# Layout_v1.net
KiCad netlist of a schematic drawn in Altium Designer
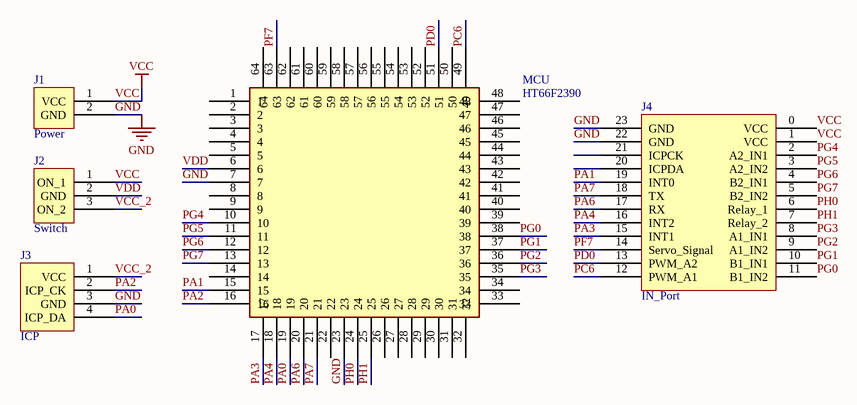
[diagram p0: Layout_v1.SchDoc]

(export (version "E")
  (design (tool "Eeschema 10.0.6"))
  (components
    (comp (ref "J1")
      (value "Power")
      (footprint "Layout_v1:Power_2P")
      (libsource (lib "Layout_v1") (part "Power"))
    )
    (comp (ref "J2")
      (value "Switch")
      (footprint "Layout_v1:Switch_3P")
      (libsource (lib "Layout_v1") (part "Switch"))
    )
    (comp (ref "J3") (value "ICP") (footprint "Layout_v1:ICP_4P") (libsource (lib "Layout_v1") (part "ICP")))
    (comp (ref "J4")
      (value "IN_Port")
      (footprint "Layout_v1:IC_Port_24P")
      (libsource (lib "Layout_v1") (part "IN_Port"))
    )
    (comp (ref "MCU")
      (value "HT66F2390")
      (footprint "Layout_v1:HT66F2390_64P")
      (libsource (lib "Layout_v1") (part "HT66F2390"))
    )
  )
  (nets
    (net (code "1") (name "/PA0") (class "Default")
      (node (ref "J3") (pin "4") (pinfunction "ICP_DA_4") (pintype "passive"))
      (node (ref "MCU") (pin "19") (pinfunction "19_19") (pintype "passive"))
    )
    (net (code "2") (name "/PA1") (class "Default")
      (node (ref "J4") (pin "19") (pinfunction "INT0_19") (pintype "passive"))
      (node (ref "MCU") (pin "15") (pinfunction "15_15") (pintype "passive"))
    )
    (net (code "3") (name "/PA2") (class "Default")
      (node (ref "J3") (pin "2") (pinfunction "ICP_CK_2") (pintype "passive"))
      (node (ref "MCU") (pin "16") (pinfunction "16_16") (pintype "passive"))
    )
    (net (code "4") (name "/PA3") (class "Default")
      (node (ref "J4") (pin "15") (pinfunction "INT1_15") (pintype "passive"))
      (node (ref "MCU") (pin "17") (pinfunction "17_17") (pintype "passive"))
    )
    (net (code "5") (name "/PA4") (class "Default")
      (node (ref "J4") (pin "16") (pinfunction "INT2_16") (pintype "passive"))
      (node (ref "MCU") (pin "18") (pinfunction "18_18") (pintype "passive"))
    )
    (net (code "6") (name "/PA6") (class "Default")
      (node (ref "J4") (pin "17") (pinfunction "RX_17") (pintype "passive"))
      (node (ref "MCU") (pin "20") (pinfunction "20_20") (pintype "passive"))
    )
    (net (code "7") (name "/PA7") (class "Default")
      (node (ref "J4") (pin "18") (pinfunction "TX_18") (pintype "passive"))
      (node (ref "MCU") (pin "21") (pinfunction "21_21") (pintype "passive"))
    )
    (net (code "8") (name "/PC6") (class "Default")
      (node (ref "J4") (pin "12") (pinfunction "PWM_A1_12") (pintype "passive"))
      (node (ref "MCU") (pin "49") (pinfunction "49_49") (pintype "passive"))
    )
    (net (code "9") (name "/PD0") (class "Default")
      (node (ref "J4") (pin "13") (pinfunction "PWM_A2_13") (pintype "passive"))
      (node (ref "MCU") (pin "51") (pinfunction "51_51") (pintype "passive"))
    )
    (net (code "10") (name "/PF7") (class "Default")
      (node (ref "J4") (pin "14") (pinfunction "Servo_Signal_14") (pintype "passive"))
      (node (ref "MCU") (pin "63") (pinfunction "63_63") (pintype "passive"))
    )
    (net (code "11") (name "/PG0") (class "Default")
      (node (ref "J4") (pin "11") (pinfunction "B1_IN2_11") (pintype "passive"))
      (node (ref "MCU") (pin "38") (pinfunction "38_38") (pintype "passive"))
    )
    (net (code "12") (name "/PG1") (class "Default")
      (node (ref "J4") (pin "10") (pinfunction "B1_IN1_10") (pintype "passive"))
      (node (ref "MCU") (pin "37") (pinfunction "37_37") (pintype "passive"))
    )
    (net (code "13") (name "/PG2") (class "Default")
      (node (ref "J4") (pin "9") (pinfunction "A1_IN2_9") (pintype "passive"))
      (node (ref "MCU") (pin "36") (pinfunction "36_36") (pintype "passive"))
    )
    (net (code "14") (name "/PG3") (class "Default")
      (node (ref "J4") (pin "8") (pinfunction "A1_IN1_8") (pintype "passive"))
      (node (ref "MCU") (pin "35") (pinfunction "35_35") (pintype "passive"))
    )
    (net (code "15") (name "/PG4") (class "Default")
      (node (ref "J4") (pin "2") (pinfunction "A2_IN1_2") (pintype "passive"))
      (node (ref "MCU") (pin "10") (pinfunction "10_10") (pintype "passive"))
    )
    (net (code "16") (name "/PG5") (class "Default")
      (node (ref "J4") (pin "3") (pinfunction "A2_IN2_3") (pintype "passive"))
      (node (ref "MCU") (pin "11") (pinfunction "11_11") (pintype "passive"))
    )
    (net (code "17") (name "/PG6") (class "Default")
      (node (ref "J4") (pin "4") (pinfunction "B2_IN1_4") (pintype "passive"))
      (node (ref "MCU") (pin "12") (pinfunction "12_12") (pintype "passive"))
    )
    (net (code "18") (name "/PG7") (class "Default")
      (node (ref "J4") (pin "5") (pinfunction "B2_IN2_5") (pintype "passive"))
      (node (ref "MCU") (pin "13") (pinfunction "13_13") (pintype "passive"))
    )
    (net (code "19") (name "/PH0") (class "Default")
      (node (ref "J4") (pin "6") (pinfunction "Relay_1_6") (pintype "passive"))
      (node (ref "MCU") (pin "24") (pinfunction "24_24") (pintype "passive"))
    )
    (net (code "20") (name "/PH1") (class "Default")
      (node (ref "J4") (pin "7") (pinfunction "Relay_2_7") (pintype "passive"))
      (node (ref "MCU") (pin "25") (pinfunction "25_25") (pintype "passive"))
    )
    (net (code "21") (name "/VCC_2") (class "Default")
      (node (ref "J2") (pin "3") (pinfunction "ON_2_3") (pintype "passive"))
      (node (ref "J3") (pin "1") (pinfunction "VCC_1") (pintype "passive"))
    )
    (net (code "22") (name "/VDD") (class "Default")
      (node (ref "J2") (pin "2") (pinfunction "GND_2") (pintype "passive"))
      (node (ref "MCU") (pin "6") (pinfunction "6_6") (pintype "passive"))
    )
    (net (code "23") (name "GND") (class "Default")
      (node (ref "J1") (pin "2") (pinfunction "GND_2") (pintype "passive"))
      (node (ref "J3") (pin "3") (pinfunction "GND_3") (pintype "passive"))
      (node (ref "J4") (pin "22") (pinfunction "GND_22") (pintype "passive"))
      (node (ref "J4") (pin "23") (pinfunction "GND_23") (pintype "passive"))
      (node (ref "MCU") (pin "23") (pinfunction "23_23") (pintype "passive"))
      (node (ref "MCU") (pin "7") (pinfunction "7_7") (pintype "passive"))
    )
    (net (code "24") (name "VCC") (class "Default")
      (node (ref "J1") (pin "1") (pinfunction "VCC_1") (pintype "passive"))
      (node (ref "J2") (pin "1") (pinfunction "ON_1_1") (pintype "passive"))
      (node (ref "J4") (pin "0") (pinfunction "VCC_0") (pintype "passive"))
      (node (ref "J4") (pin "1") (pinfunction "VCC_1") (pintype "passive"))
    )
    (net (code "25") (name "unconnected-(J4-ICPCK-Pad21)") (class "Default")
      (node (ref "J4") (pin "21") (pinfunction "ICPCK_21") (pintype "passive"))
    )
    (net (code "26") (name "unconnected-(J4-ICPDA-Pad20)") (class "Default")
      (node (ref "J4") (pin "20") (pinfunction "ICPDA_20") (pintype "passive"))
    )
    (net (code "27") (name "unconnected-(MCU-Pad1)") (class "Default")
      (node (ref "MCU") (pin "1") (pinfunction "1_1") (pintype "passive"))
    )
    (net (code "28") (name "unconnected-(MCU-Pad2)") (class "Default")
      (node (ref "MCU") (pin "2") (pinfunction "2_2") (pintype "passive"))
    )
    (net (code "29") (name "unconnected-(MCU-Pad3)") (class "Default")
      (node (ref "MCU") (pin "3") (pinfunction "3_3") (pintype "passive"))
    )
    (net (code "30") (name "unconnected-(MCU-Pad4)") (class "Default")
      (node (ref "MCU") (pin "4") (pinfunction "4_4") (pintype "passive"))
    )
    (net (code "31") (name "unconnected-(MCU-Pad5)") (class "Default")
      (node (ref "MCU") (pin "5") (pinfunction "5_5") (pintype "passive"))
    )
    (net (code "32") (name "unconnected-(MCU-Pad8)") (class "Default")
      (node (ref "MCU") (pin "8") (pinfunction "8_8") (pintype "passive"))
    )
    (net (code "33") (name "unconnected-(MCU-Pad9)") (class "Default")
      (node (ref "MCU") (pin "9") (pinfunction "9_9") (pintype "passive"))
    )
    (net (code "34") (name "unconnected-(MCU-Pad14)") (class "Default")
      (node (ref "MCU") (pin "14") (pinfunction "14_14") (pintype "passive"))
    )
    (net (code "35") (name "unconnected-(MCU-Pad22)") (class "Default")
      (node (ref "MCU") (pin "22") (pinfunction "22_22") (pintype "passive"))
    )
    (net (code "36") (name "unconnected-(MCU-Pad26)") (class "Default")
      (node (ref "MCU") (pin "26") (pinfunction "26_26") (pintype "passive"))
    )
    (net (code "37") (name "unconnected-(MCU-Pad27)") (class "Default")
      (node (ref "MCU") (pin "27") (pinfunction "27_27") (pintype "passive"))
    )
    (net (code "38") (name "unconnected-(MCU-Pad28)") (class "Default")
      (node (ref "MCU") (pin "28") (pinfunction "28_28") (pintype "passive"))
    )
    (net (code "39") (name "unconnected-(MCU-Pad29)") (class "Default")
      (node (ref "MCU") (pin "29") (pinfunction "29_29") (pintype "passive"))
    )
    (net (code "40") (name "unconnected-(MCU-Pad30)") (class "Default")
      (node (ref "MCU") (pin "30") (pinfunction "30_30") (pintype "passive"))
    )
    (net (code "41") (name "unconnected-(MCU-Pad31)") (class "Default")
      (node (ref "MCU") (pin "31") (pinfunction "31_31") (pintype "passive"))
    )
    (net (code "42") (name "unconnected-(MCU-Pad32)") (class "Default")
      (node (ref "MCU") (pin "32") (pinfunction "32_32") (pintype "passive"))
    )
    (net (code "43") (name "unconnected-(MCU-Pad33)") (class "Default")
      (node (ref "MCU") (pin "33") (pinfunction "33_33") (pintype "passive"))
    )
    (net (code "44") (name "unconnected-(MCU-Pad34)") (class "Default")
      (node (ref "MCU") (pin "34") (pinfunction "34_34") (pintype "passive"))
    )
    (net (code "45") (name "unconnected-(MCU-Pad39)") (class "Default")
      (node (ref "MCU") (pin "39") (pinfunction "39_39") (pintype "passive"))
    )
    (net (code "46") (name "unconnected-(MCU-Pad40)") (class "Default")
      (node (ref "MCU") (pin "40") (pinfunction "40_40") (pintype "passive"))
    )
    (net (code "47") (name "unconnected-(MCU-Pad41)") (class "Default")
      (node (ref "MCU") (pin "41") (pinfunction "41_41") (pintype "passive"))
    )
    (net (code "48") (name "unconnected-(MCU-Pad42)") (class "Default")
      (node (ref "MCU") (pin "42") (pinfunction "42_42") (pintype "passive"))
    )
    (net (code "49") (name "unconnected-(MCU-Pad43)") (class "Default")
      (node (ref "MCU") (pin "43") (pinfunction "43_43") (pintype "passive"))
    )
    (net (code "50") (name "unconnected-(MCU-Pad44)") (class "Default")
      (node (ref "MCU") (pin "44") (pinfunction "44_44") (pintype "passive"))
    )
    (net (code "51") (name "unconnected-(MCU-Pad45)") (class "Default")
      (node (ref "MCU") (pin "45") (pinfunction "45_45") (pintype "passive"))
    )
    (net (code "52") (name "unconnected-(MCU-Pad46)") (class "Default")
      (node (ref "MCU") (pin "46") (pinfunction "46_46") (pintype "passive"))
    )
    (net (code "53") (name "unconnected-(MCU-Pad47)") (class "Default")
      (node (ref "MCU") (pin "47") (pinfunction "47_47") (pintype "passive"))
    )
    (net (code "54") (name "unconnected-(MCU-Pad48)") (class "Default")
      (node (ref "MCU") (pin "48") (pinfunction "48_48") (pintype "passive"))
    )
    (net (code "55") (name "unconnected-(MCU-Pad50)") (class "Default")
      (node (ref "MCU") (pin "50") (pinfunction "50_50") (pintype "passive"))
    )
    (net (code "56") (name "unconnected-(MCU-Pad52)") (class "Default")
      (node (ref "MCU") (pin "52") (pinfunction "52_52") (pintype "passive"))
    )
    (net (code "57") (name "unconnected-(MCU-Pad53)") (class "Default")
      (node (ref "MCU") (pin "53") (pinfunction "53_53") (pintype "passive"))
    )
    (net (code "58") (name "unconnected-(MCU-Pad54)") (class "Default")
      (node (ref "MCU") (pin "54") (pinfunction "54_54") (pintype "passive"))
    )
    (net (code "59") (name "unconnected-(MCU-Pad55)") (class "Default")
      (node (ref "MCU") (pin "55") (pinfunction "55_55") (pintype "passive"))
    )
    (net (code "60") (name "unconnected-(MCU-Pad56)") (class "Default")
      (node (ref "MCU") (pin "56") (pinfunction "56_56") (pintype "passive"))
    )
    (net (code "61") (name "unconnected-(MCU-Pad57)") (class "Default")
      (node (ref "MCU") (pin "57") (pinfunction "57_57") (pintype "passive"))
    )
    (net (code "62") (name "unconnected-(MCU-Pad58)") (class "Default")
      (node (ref "MCU") (pin "58") (pinfunction "58_58") (pintype "passive"))
    )
    (net (code "63") (name "unconnected-(MCU-Pad59)") (class "Default")
      (node (ref "MCU") (pin "59") (pinfunction "59_59") (pintype "passive"))
    )
    (net (code "64") (name "unconnected-(MCU-Pad60)") (class "Default")
      (node (ref "MCU") (pin "60") (pinfunction "60_60") (pintype "passive"))
    )
    (net (code "65") (name "unconnected-(MCU-Pad61)") (class "Default")
      (node (ref "MCU") (pin "61") (pinfunction "61_61") (pintype "passive"))
    )
    (net (code "66") (name "unconnected-(MCU-Pad62)") (class "Default")
      (node (ref "MCU") (pin "62") (pinfunction "62_62") (pintype "passive"))
    )
    (net (code "67") (name "unconnected-(MCU-Pad64)") (class "Default")
      (node (ref "MCU") (pin "64") (pinfunction "64_64") (pintype "passive"))
    )
  )
)
